# tm8_racingStripes.net
KiCad netlist of a schematic drawn in EAGLE
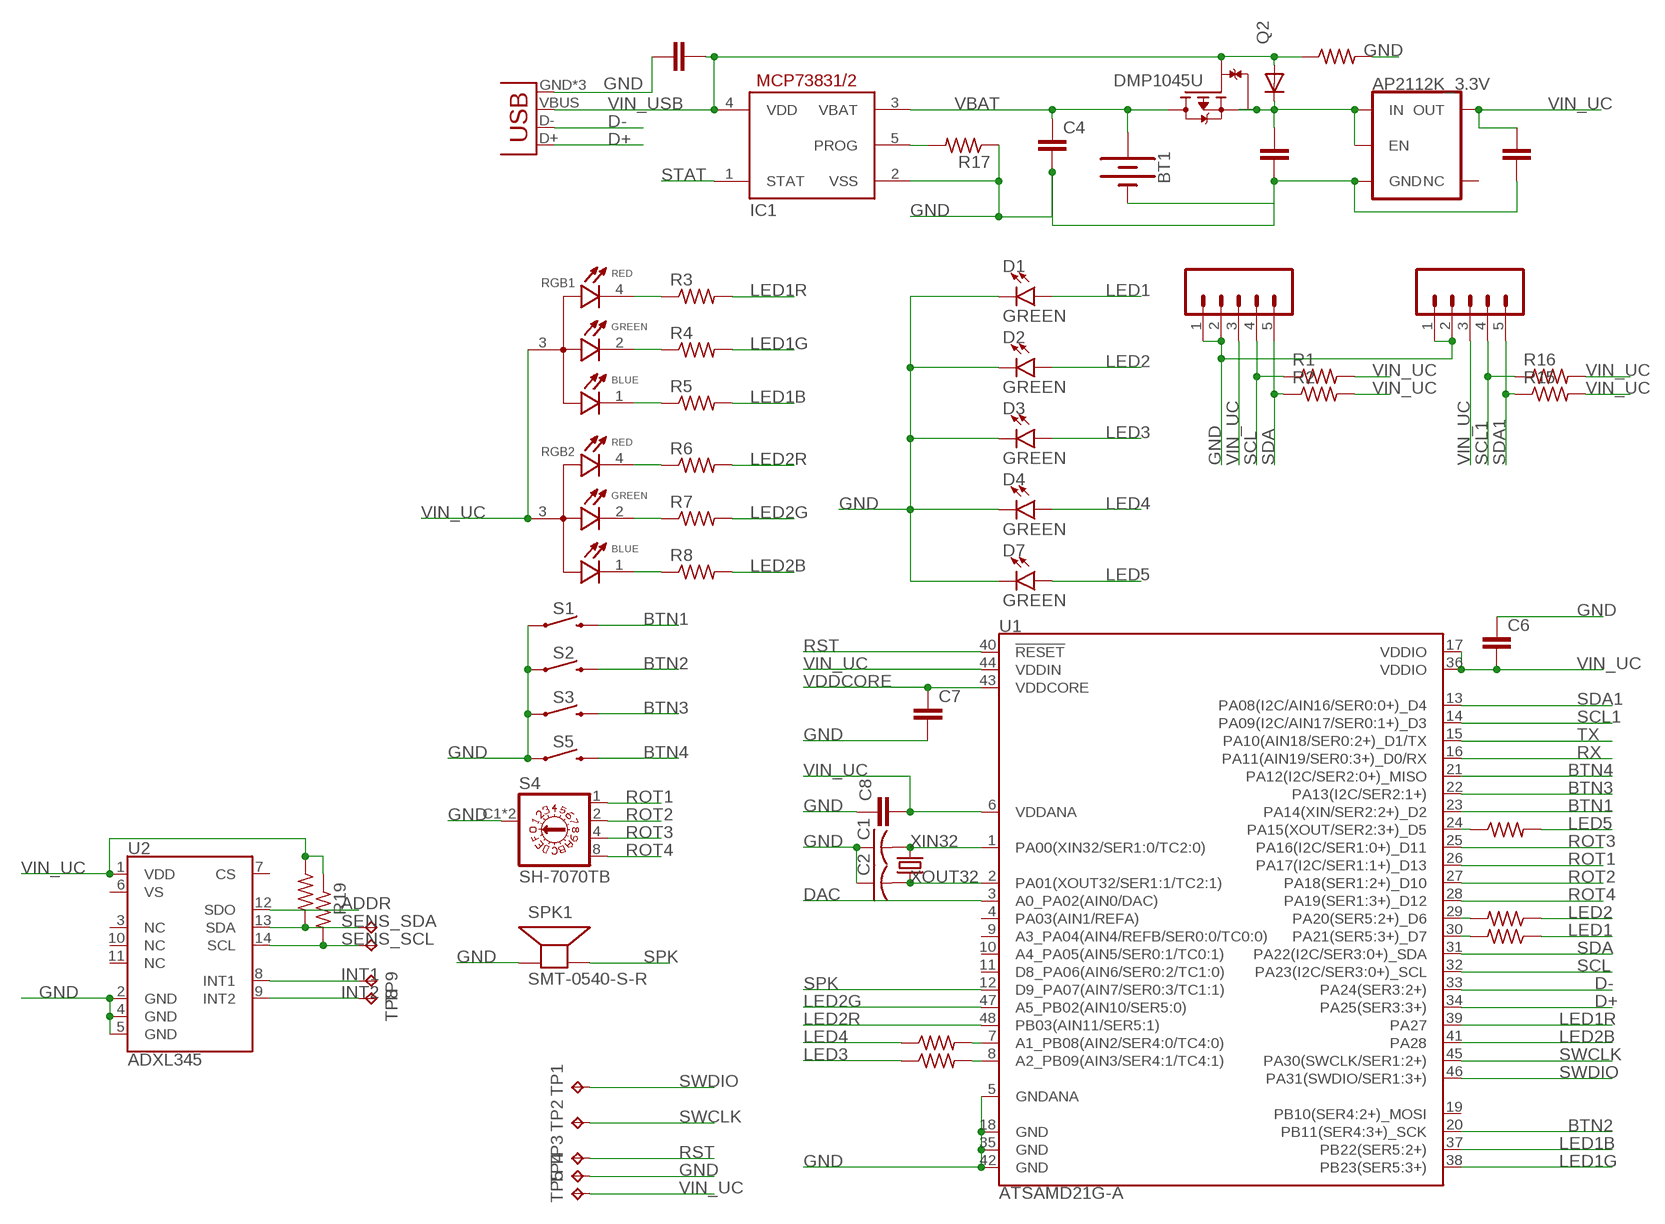
[diagram p0: schematic, sheet 1]

(export (version "E")
  (design (tool "Eeschema 10.0.6"))
  (components
    (comp (ref "AP2112K_3.3V")
      (value "3.3V")
      (footprint "eagle-import:SOT23-5")
      (libsource (lib "eagle-import") (part "V_REG_AP2112K-3.3V"))
    )
    (comp (ref "BT1")
      (value "BATTERY-20MM_SMD_4LEGS_OVERPASTE_INNER")
      (footprint "eagle-import:BATTCON_20MM_4LEGS_OVERPASTE_INNER")
      (libsource (lib "eagle-import") (part "BATTERY-20MM_SMD_4LEGS_OVERPASTE_INNER"))
    )
    (comp (ref "C1")
      (value "C-USC0603")
      (footprint "eagle-import:C0603")
      (libsource (lib "eagle-import") (part "C-USC0603"))
    )
    (comp (ref "C2")
      (value "C-USC0603")
      (footprint "eagle-import:C0603")
      (libsource (lib "eagle-import") (part "C-USC0603"))
    )
    (comp (ref "C3")
      (value "C-EUC0603")
      (footprint "eagle-import:C0603")
      (libsource (lib "eagle-import") (part "C-EUC0603"))
    )
    (comp (ref "C4")
      (value "C-EUC0603")
      (footprint "eagle-import:C0603")
      (libsource (lib "eagle-import") (part "C-EUC0603"))
    )
    (comp (ref "C5")
      (value "C-EUC0603")
      (footprint "eagle-import:C0603")
      (libsource (lib "eagle-import") (part "C-EUC0603"))
    )
    (comp (ref "C6")
      (value "C-EUC0603")
      (footprint "eagle-import:C0603")
      (libsource (lib "eagle-import") (part "C-EUC0603"))
    )
    (comp (ref "C7")
      (value "C-EUC0603")
      (footprint "eagle-import:C0603")
      (libsource (lib "eagle-import") (part "C-EUC0603"))
    )
    (comp (ref "C8")
      (value "C-EUC0603")
      (footprint "eagle-import:C0603")
      (libsource (lib "eagle-import") (part "C-EUC0603"))
    )
    (comp (ref "C9")
      (value "C-EUC0603")
      (footprint "eagle-import:C0603")
      (libsource (lib "eagle-import") (part "C-EUC0603"))
    )
    (comp (ref "D1")
      (value "GREEN")
      (footprint "eagle-import:LED-1206")
      (libsource (lib "eagle-import") (part "LED-GREEN1206"))
    )
    (comp (ref "D2")
      (value "GREEN")
      (footprint "eagle-import:LED-1206")
      (libsource (lib "eagle-import") (part "LED-GREEN1206"))
    )
    (comp (ref "D3")
      (value "GREEN")
      (footprint "eagle-import:LED-1206")
      (libsource (lib "eagle-import") (part "LED-GREEN1206"))
    )
    (comp (ref "D4")
      (value "GREEN")
      (footprint "eagle-import:LED-1206")
      (libsource (lib "eagle-import") (part "LED-GREEN1206"))
    )
    (comp (ref "D7")
      (value "GREEN")
      (footprint "eagle-import:LED-1206")
      (libsource (lib "eagle-import") (part "LED-GREEN1206"))
    )
    (comp (ref "D8")
      (value "DIODESOD-323F")
      (footprint "eagle-import:SOD-323F")
      (libsource (lib "eagle-import") (part "DIODESOD-323F"))
    )
    (comp (ref "IC1")
      (value "MCP73831/OT")
      (footprint "eagle-import:SOT23-5L")
      (libsource (lib "eagle-import") (part "MCP73831/OT"))
    )
    (comp (ref "JP2")
      (value "USB-MICROB")
      (footprint "eagle-import:USB-MICROB")
      (libsource (lib "eagle-import") (part "USB-MICROB"))
    )
    (comp (ref "LCD1")
      (value "CONN_05VERT_FEMALE_HEADER")
      (footprint "eagle-import:1X05_SMD_VERTICAL_COMBO")
      (libsource (lib "eagle-import") (part "CONN_05VERT_FEMALE_HEADER"))
    )
    (comp (ref "LCD2")
      (value "CONN_05VERT_FEMALE_HEADER")
      (footprint "eagle-import:1X05_SMD_VERTICAL_COMBO")
      (libsource (lib "eagle-import") (part "CONN_05VERT_FEMALE_HEADER"))
    )
    (comp (ref "Q2")
      (value "DMP1045U")
      (footprint "eagle-import:SOT91P240X110-3N")
      (fields (field (name "MF") "Diodes Inc."))
      (libsource (lib "eagle-import") (part "DMP1045U"))
    )
    (comp (ref "R1")
      (value "R-US_R0603")
      (footprint "eagle-import:R0603")
      (libsource (lib "eagle-import") (part "rcl_334_R-US_R0603"))
    )
    (comp (ref "R2")
      (value "R-US_R0603")
      (footprint "eagle-import:R0603")
      (libsource (lib "eagle-import") (part "rcl_334_R-US_R0603"))
    )
    (comp (ref "R3")
      (value "R-US_R0603")
      (footprint "eagle-import:R0603")
      (libsource (lib "eagle-import") (part "rcl_334_R-US_R0603"))
    )
    (comp (ref "R4")
      (value "R-US_R0603")
      (footprint "eagle-import:R0603")
      (libsource (lib "eagle-import") (part "rcl_334_R-US_R0603"))
    )
    (comp (ref "R5")
      (value "R-US_R0603")
      (footprint "eagle-import:R0603")
      (libsource (lib "eagle-import") (part "rcl_334_R-US_R0603"))
    )
    (comp (ref "R6")
      (value "R-US_R0603")
      (footprint "eagle-import:R0603")
      (libsource (lib "eagle-import") (part "rcl_334_R-US_R0603"))
    )
    (comp (ref "R7")
      (value "R-US_R0603")
      (footprint "eagle-import:R0603")
      (libsource (lib "eagle-import") (part "rcl_334_R-US_R0603"))
    )
    (comp (ref "R8")
      (value "R-US_R0603")
      (footprint "eagle-import:R0603")
      (libsource (lib "eagle-import") (part "rcl_334_R-US_R0603"))
    )
    (comp (ref "R9")
      (value "R-US_R0603")
      (footprint "eagle-import:R0603")
      (libsource (lib "eagle-import") (part "rcl_334_R-US_R0603"))
    )
    (comp (ref "R10")
      (value "R-US_R0603")
      (footprint "eagle-import:R0603")
      (libsource (lib "eagle-import") (part "rcl_334_R-US_R0603"))
    )
    (comp (ref "R11")
      (value "R-US_R0603")
      (footprint "eagle-import:R0603")
      (libsource (lib "eagle-import") (part "rcl_334_R-US_R0603"))
    )
    (comp (ref "R12")
      (value "R-US_R0603")
      (footprint "eagle-import:R0603")
      (libsource (lib "eagle-import") (part "rcl_334_R-US_R0603"))
    )
    (comp (ref "R13")
      (value "R-US_R0603")
      (footprint "eagle-import:R0603")
      (libsource (lib "eagle-import") (part "rcl_334_R-US_R0603"))
    )
    (comp (ref "R14")
      (value "R-US_R0603")
      (footprint "eagle-import:R0603")
      (libsource (lib "eagle-import") (part "R-US_R0603"))
    )
    (comp (ref "R15")
      (value "R-US_R0603")
      (footprint "eagle-import:R0603")
      (libsource (lib "eagle-import") (part "rcl_334_R-US_R0603"))
    )
    (comp (ref "R16")
      (value "R-US_R0603")
      (footprint "eagle-import:R0603")
      (libsource (lib "eagle-import") (part "rcl_334_R-US_R0603"))
    )
    (comp (ref "R17")
      (value "R-US_R0603")
      (footprint "eagle-import:R0603")
      (libsource (lib "eagle-import") (part "adafruit_25768682_R-US_R0603"))
    )
    (comp (ref "R18")
      (value "R-US_R0603")
      (footprint "eagle-import:R0603")
      (libsource (lib "eagle-import") (part "rcl_334_R-US_R0603"))
    )
    (comp (ref "R19")
      (value "R-US_R0603")
      (footprint "eagle-import:R0603")
      (libsource (lib "eagle-import") (part "rcl_334_R-US_R0603"))
    )
    (comp (ref "RGB1")
      (value "EAST1616RGBA3")
      (footprint "eagle-import:LED_EAST1616RGBA3")
      (fields (field (name "MF") "Everlight Electronics"))
      (libsource (lib "eagle-import") (part "EAST1616RGBA3"))
    )
    (comp (ref "RGB2")
      (value "EAST1616RGBA3")
      (footprint "eagle-import:LED_EAST1616RGBA3")
      (fields (field (name "MF") "Everlight Electronics"))
      (libsource (lib "eagle-import") (part "EAST1616RGBA3"))
    )
    (comp (ref "S1")
      (value "MOMENTARY-SWITCH-SPST-SMD-6.0X3.5MM")
      (footprint "eagle-import:TACTILE_SWITCH_SMD_6.0X3.5MM")
      (libsource (lib "eagle-import") (part "MOMENTARY-SWITCH-SPST-SMD-6.0X3.5MM"))
    )
    (comp (ref "S2")
      (value "MOMENTARY-SWITCH-SPST-SMD-6.0X3.5MM")
      (footprint "eagle-import:TACTILE_SWITCH_SMD_6.0X3.5MM")
      (libsource (lib "eagle-import") (part "MOMENTARY-SWITCH-SPST-SMD-6.0X3.5MM"))
    )
    (comp (ref "S3")
      (value "MOMENTARY-SWITCH-SPST-SMD-6.0X3.5MM")
      (footprint "eagle-import:TACTILE_SWITCH_SMD_6.0X3.5MM")
      (libsource (lib "eagle-import") (part "MOMENTARY-SWITCH-SPST-SMD-6.0X3.5MM"))
    )
    (comp (ref "S4")
      (value "SH-7070TB")
      (footprint "eagle-import:SH-7070B")
      (fields (field (name "MF") "Nidec Copal"))
      (libsource (lib "eagle-import") (part "SH-7070TB"))
    )
    (comp (ref "S5")
      (value "MOMENTARY-SWITCH-SPST-SMD-6.0X3.5MM")
      (footprint "eagle-import:TACTILE_SWITCH_SMD_6.0X3.5MM")
      (libsource (lib "eagle-import") (part "MOMENTARY-SWITCH-SPST-SMD-6.0X3.5MM"))
    )
    (comp (ref "SPK1")
      (value "SMT-0540-S-R")
      (footprint "eagle-import:SMT-0540-S-R")
      (fields (field (name "MF") "PUI"))
      (libsource (lib "eagle-import") (part "SMT-0540-S-R"))
    )
    (comp (ref "TP1")
      (value "TPTP10R")
      (footprint "eagle-import:TP10R")
      (libsource (lib "eagle-import") (part "TPTP10R"))
    )
    (comp (ref "TP2")
      (value "TPTP10R")
      (footprint "eagle-import:TP10R")
      (libsource (lib "eagle-import") (part "TPTP10R"))
    )
    (comp (ref "TP3")
      (value "TPTP10R")
      (footprint "eagle-import:TP10R")
      (libsource (lib "eagle-import") (part "TPTP10R"))
    )
    (comp (ref "TP4")
      (value "TPTP10R")
      (footprint "eagle-import:TP10R")
      (libsource (lib "eagle-import") (part "TPTP10R"))
    )
    (comp (ref "TP5")
      (value "TPTP10R")
      (footprint "eagle-import:TP10R")
      (libsource (lib "eagle-import") (part "TPTP10R"))
    )
    (comp (ref "TP6")
      (value "TPTP10R")
      (footprint "eagle-import:TP10R")
      (libsource (lib "eagle-import") (part "TPTP10R"))
    )
    (comp (ref "TP7")
      (value "TPTP10R")
      (footprint "eagle-import:TP10R")
      (libsource (lib "eagle-import") (part "TPTP10R"))
    )
    (comp (ref "TP8")
      (value "TPTP10R")
      (footprint "eagle-import:TP10R")
      (libsource (lib "eagle-import") (part "TPTP10R"))
    )
    (comp (ref "TP9")
      (value "TPTP10R")
      (footprint "eagle-import:TP10R")
      (libsource (lib "eagle-import") (part "TPTP10R"))
    )
    (comp (ref "U1")
      (value "ATSAMD21G-A")
      (footprint "eagle-import:TQFP-48")
      (libsource (lib "eagle-import") (part "ATSAMD21G-A"))
    )
    (comp (ref "U2")
      (value "ADXL345")
      (footprint "eagle-import:LGA-14")
      (libsource (lib "eagle-import") (part "ADXL345"))
    )
    (comp (ref "Y1")
      (value "32.768kHz")
      (footprint "eagle-import:CRYSTAL-SMD-3.2X1.5MM")
      (libsource (lib "eagle-import") (part "CRYSTAL-32.768KHZSMD-3.2X1.5"))
    )
  )
  (nets
    (net (code "1") (name "/ADDR") (class "Default")
      (node (ref "U2") (pin "12") (pinfunction "SDO_12") (pintype "bidirectional"))
    )
    (net (code "2") (name "/BTN1") (class "Default")
      (node (ref "S1") (pin "2") (pinfunction "2_2") (pintype "passive"))
      (node (ref "U1") (pin "23") (pinfunction "PA14(XIN/SER2:2+)_D2_23") (pintype "bidirectional"))
    )
    (net (code "3") (name "/BTN2") (class "Default")
      (node (ref "S2") (pin "2") (pinfunction "2_2") (pintype "passive"))
      (node (ref "U1") (pin "20") (pinfunction "PB11(SER4:3+)_SCK_20") (pintype "bidirectional"))
    )
    (net (code "4") (name "/BTN3") (class "Default")
      (node (ref "S3") (pin "2") (pinfunction "2_2") (pintype "passive"))
      (node (ref "U1") (pin "22") (pinfunction "PA13(I2C/SER2:1+)_22") (pintype "bidirectional"))
    )
    (net (code "5") (name "/BTN4") (class "Default")
      (node (ref "S5") (pin "2") (pinfunction "2_2") (pintype "passive"))
      (node (ref "U1") (pin "21") (pinfunction "PA12(I2C/SER2:0+)_MISO_21") (pintype "bidirectional"))
    )
    (net (code "6") (name "/D+") (class "Default")
      (node (ref "JP2") (pin "D+") (pinfunction "D+_D+") (pintype "bidirectional"))
      (node (ref "U1") (pin "34") (pinfunction "PA25(SER3:3+)_34") (pintype "bidirectional"))
    )
    (net (code "7") (name "/D-") (class "Default")
      (node (ref "JP2") (pin "D-") (pinfunction "D-_D-") (pintype "bidirectional"))
      (node (ref "U1") (pin "33") (pinfunction "PA24(SER3:2+)_33") (pintype "bidirectional"))
    )
    (net (code "8") (name "/DAC") (class "Default")
      (node (ref "U1") (pin "3") (pinfunction "A0_PA02(AIN0/DAC)_3") (pintype "bidirectional"))
    )
    (net (code "9") (name "/GND") (class "Default")
      (node (ref "AP2112K_3.3V") (pin "2") (pinfunction "GND_2") (pintype "input"))
      (node (ref "BT1") (pin "2") (pinfunction "-_2") (pintype "power_in"))
      (node (ref "C1") (pin "1") (pinfunction "1_1") (pintype "passive"))
      (node (ref "C2") (pin "1") (pinfunction "1_1") (pintype "passive"))
      (node (ref "C3") (pin "1") (pinfunction "1_1") (pintype "passive"))
      (node (ref "C4") (pin "2") (pinfunction "2_2") (pintype "passive"))
      (node (ref "C5") (pin "2") (pinfunction "2_2") (pintype "passive"))
      (node (ref "C6") (pin "1") (pinfunction "1_1") (pintype "passive"))
      (node (ref "C7") (pin "2") (pinfunction "2_2") (pintype "passive"))
      (node (ref "C8") (pin "1") (pinfunction "1_1") (pintype "passive"))
      (node (ref "C9") (pin "2") (pinfunction "2_2") (pintype "passive"))
      (node (ref "D1") (pin "C") (pinfunction "C_C") (pintype "passive"))
      (node (ref "D2") (pin "C") (pinfunction "C_C") (pintype "passive"))
      (node (ref "D3") (pin "C") (pinfunction "C_C") (pintype "passive"))
      (node (ref "D4") (pin "C") (pinfunction "C_C") (pintype "passive"))
      (node (ref "D7") (pin "C") (pinfunction "C_C") (pintype "passive"))
      (node (ref "IC1") (pin "2") (pinfunction "VSS_2") (pintype "power_in"))
      (node (ref "JP2") (pin "GND") (pinfunction "GND_GND") (pintype "bidirectional"))
      (node (ref "JP2") (pin "MT1") (pinfunction "GND_MT1") (pintype "bidirectional"))
      (node (ref "JP2") (pin "MT2") (pinfunction "GND_MT2") (pintype "bidirectional"))
      (node (ref "LCD1") (pin "1") (pinfunction "1_1") (pintype "passive"))
      (node (ref "LCD1") (pin "2") (pinfunction "2_2") (pintype "passive"))
      (node (ref "LCD2") (pin "1") (pinfunction "1_1") (pintype "passive"))
      (node (ref "LCD2") (pin "2") (pinfunction "2_2") (pintype "passive"))
      (node (ref "R14") (pin "2") (pinfunction "2_2") (pintype "passive"))
      (node (ref "R17") (pin "1") (pinfunction "1_1") (pintype "passive"))
      (node (ref "S1") (pin "1") (pinfunction "1_1") (pintype "passive"))
      (node (ref "S2") (pin "1") (pinfunction "1_1") (pintype "passive"))
      (node (ref "S3") (pin "1") (pinfunction "1_1") (pintype "passive"))
      (node (ref "S4") (pin "C1") (pinfunction "C_C1") (pintype "passive"))
      (node (ref "S4") (pin "C2") (pinfunction "C_C2") (pintype "passive"))
      (node (ref "S5") (pin "1") (pinfunction "1_1") (pintype "passive"))
      (node (ref "SPK1") (pin "-") (pinfunction "+_-") (pintype "passive"))
      (node (ref "TP4") (pin "TP") (pinfunction "TP_TP") (pintype "input"))
      (node (ref "U1") (pin "18") (pinfunction "GND_18") (pintype "bidirectional"))
      (node (ref "U1") (pin "35") (pinfunction "GND_35") (pintype "bidirectional"))
      (node (ref "U1") (pin "42") (pinfunction "GND_42") (pintype "bidirectional"))
      (node (ref "U1") (pin "5") (pinfunction "GNDANA_5") (pintype "bidirectional"))
      (node (ref "U2") (pin "2") (pinfunction "GND_2") (pintype "bidirectional"))
      (node (ref "U2") (pin "4") (pinfunction "GND_4") (pintype "bidirectional"))
      (node (ref "U2") (pin "5") (pinfunction "GND_5") (pintype "bidirectional"))
    )
    (net (code "10") (name "/INT1") (class "Default")
      (node (ref "TP9") (pin "TP") (pinfunction "TP_TP") (pintype "input"))
      (node (ref "U2") (pin "8") (pinfunction "INT1_8") (pintype "bidirectional"))
    )
    (net (code "11") (name "/INT2") (class "Default")
      (node (ref "TP8") (pin "TP") (pinfunction "TP_TP") (pintype "input"))
      (node (ref "U2") (pin "9") (pinfunction "INT2_9") (pintype "bidirectional"))
    )
    (net (code "12") (name "/LED1") (class "Default")
      (node (ref "D1") (pin "A") (pinfunction "A_A") (pintype "passive"))
      (node (ref "R9") (pin "1") (pinfunction "1_1") (pintype "passive"))
    )
    (net (code "13") (name "/LED1B") (class "Default")
      (node (ref "R5") (pin "2") (pinfunction "2_2") (pintype "passive"))
      (node (ref "U1") (pin "37") (pinfunction "PB22(SER5:2+)_37") (pintype "bidirectional"))
    )
    (net (code "14") (name "/LED1G") (class "Default")
      (node (ref "R4") (pin "2") (pinfunction "2_2") (pintype "passive"))
      (node (ref "U1") (pin "38") (pinfunction "PB23(SER5:3+)_38") (pintype "bidirectional"))
    )
    (net (code "15") (name "/LED1R") (class "Default")
      (node (ref "R3") (pin "2") (pinfunction "2_2") (pintype "passive"))
      (node (ref "U1") (pin "39") (pinfunction "PA27_39") (pintype "bidirectional"))
    )
    (net (code "16") (name "/LED2") (class "Default")
      (node (ref "D2") (pin "A") (pinfunction "A_A") (pintype "passive"))
      (node (ref "R10") (pin "1") (pinfunction "1_1") (pintype "passive"))
    )
    (net (code "17") (name "/LED2B") (class "Default")
      (node (ref "R8") (pin "2") (pinfunction "2_2") (pintype "passive"))
      (node (ref "U1") (pin "41") (pinfunction "PA28_41") (pintype "bidirectional"))
    )
    (net (code "18") (name "/LED2G") (class "Default")
      (node (ref "R7") (pin "2") (pinfunction "2_2") (pintype "passive"))
      (node (ref "U1") (pin "47") (pinfunction "A5_PB02(AIN10/SER5:0)_47") (pintype "bidirectional"))
    )
    (net (code "19") (name "/LED2R") (class "Default")
      (node (ref "R6") (pin "2") (pinfunction "2_2") (pintype "passive"))
      (node (ref "U1") (pin "48") (pinfunction "PB03(AIN11/SER5:1)_48") (pintype "bidirectional"))
    )
    (net (code "20") (name "/LED3") (class "Default")
      (node (ref "D3") (pin "A") (pinfunction "A_A") (pintype "passive"))
      (node (ref "R11") (pin "1") (pinfunction "1_1") (pintype "passive"))
    )
    (net (code "21") (name "/LED4") (class "Default")
      (node (ref "D4") (pin "A") (pinfunction "A_A") (pintype "passive"))
      (node (ref "R12") (pin "1") (pinfunction "1_1") (pintype "passive"))
    )
    (net (code "22") (name "/LED5") (class "Default")
      (node (ref "D7") (pin "A") (pinfunction "A_A") (pintype "passive"))
      (node (ref "R13") (pin "2") (pinfunction "2_2") (pintype "passive"))
    )
    (net (code "23") (name "/ROT1") (class "Default")
      (node (ref "S4") (pin "1") (pinfunction "1_1") (pintype "passive"))
      (node (ref "U1") (pin "26") (pinfunction "PA17(I2C/SER1:1+)_D13_26") (pintype "bidirectional"))
    )
    (net (code "24") (name "/ROT2") (class "Default")
      (node (ref "S4") (pin "2") (pinfunction "2_2") (pintype "passive"))
      (node (ref "U1") (pin "27") (pinfunction "PA18(SER1:2+)_D10_27") (pintype "bidirectional"))
    )
    (net (code "25") (name "/ROT3") (class "Default")
      (node (ref "S4") (pin "4") (pinfunction "4_4") (pintype "passive"))
      (node (ref "U1") (pin "25") (pinfunction "PA16(I2C/SER1:0+)_D11_25") (pintype "bidirectional"))
    )
    (net (code "26") (name "/ROT4") (class "Default")
      (node (ref "S4") (pin "8") (pinfunction "8_8") (pintype "passive"))
      (node (ref "U1") (pin "28") (pinfunction "PA19(SER1:3+)_D12_28") (pintype "bidirectional"))
    )
    (net (code "27") (name "/RST") (class "Default")
      (node (ref "TP3") (pin "TP") (pinfunction "TP_TP") (pintype "input"))
      (node (ref "U1") (pin "40") (pinfunction "~{RESET}_40") (pintype "bidirectional"))
    )
    (net (code "28") (name "/RX") (class "Default")
      (node (ref "U1") (pin "16") (pinfunction "PA11(AIN19/SER0:3+)_D0/RX_16") (pintype "bidirectional"))
    )
    (net (code "29") (name "/SCL") (class "Default")
      (node (ref "LCD1") (pin "4") (pinfunction "4_4") (pintype "passive"))
      (node (ref "R1") (pin "1") (pinfunction "1_1") (pintype "passive"))
      (node (ref "U1") (pin "32") (pinfunction "PA23(I2C/SER3:0+)_SCL_32") (pintype "bidirectional"))
    )
    (net (code "30") (name "/SCL1") (class "Default")
      (node (ref "LCD2") (pin "4") (pinfunction "4_4") (pintype "passive"))
      (node (ref "R16") (pin "1") (pinfunction "1_1") (pintype "passive"))
      (node (ref "U1") (pin "14") (pinfunction "PA09(I2C/AIN17/SER0:1+)_D3_14") (pintype "bidirectional"))
    )
    (net (code "31") (name "/SDA") (class "Default")
      (node (ref "LCD1") (pin "5") (pinfunction "5_5") (pintype "passive"))
      (node (ref "R2") (pin "1") (pinfunction "1_1") (pintype "passive"))
      (node (ref "U1") (pin "31") (pinfunction "PA22(I2C/SER3:0+)_SDA_31") (pintype "bidirectional"))
    )
    (net (code "32") (name "/SDA1") (class "Default")
      (node (ref "LCD2") (pin "5") (pinfunction "5_5") (pintype "passive"))
      (node (ref "R15") (pin "1") (pinfunction "1_1") (pintype "passive"))
      (node (ref "U1") (pin "13") (pinfunction "PA08(I2C/AIN16/SER0:0+)_D4_13") (pintype "bidirectional"))
    )
    (net (code "33") (name "/SENS_SCL") (class "Default")
      (node (ref "R19") (pin "2") (pinfunction "2_2") (pintype "passive"))
      (node (ref "TP6") (pin "TP") (pinfunction "TP_TP") (pintype "input"))
      (node (ref "U2") (pin "14") (pinfunction "SCL_14") (pintype "bidirectional"))
    )
    (net (code "34") (name "/SENS_SDA") (class "Default")
      (node (ref "R18") (pin "2") (pinfunction "2_2") (pintype "passive"))
      (node (ref "TP7") (pin "TP") (pinfunction "TP_TP") (pintype "input"))
      (node (ref "U2") (pin "13") (pinfunction "SDA_13") (pintype "bidirectional"))
    )
    (net (code "35") (name "/SPK") (class "Default")
      (node (ref "SPK1") (pin "+") (pinfunction "-_+") (pintype "passive"))
      (node (ref "U1") (pin "12") (pinfunction "D9_PA07(AIN7/SER0:3/TC1:1)_12") (pintype "bidirectional"))
    )
    (net (code "36") (name "/STAT") (class "Default")
      (node (ref "IC1") (pin "1") (pinfunction "STAT_1") (pintype "output"))
    )
    (net (code "37") (name "/SWCLK") (class "Default")
      (node (ref "TP2") (pin "TP") (pinfunction "TP_TP") (pintype "input"))
      (node (ref "U1") (pin "45") (pinfunction "PA30(SWCLK/SER1:2+)_45") (pintype "bidirectional"))
    )
    (net (code "38") (name "/SWDIO") (class "Default")
      (node (ref "TP1") (pin "TP") (pinfunction "TP_TP") (pintype "input"))
      (node (ref "U1") (pin "46") (pinfunction "PA31(SWDIO/SER1:3+)_46") (pintype "bidirectional"))
    )
    (net (code "39") (name "/TX") (class "Default")
      (node (ref "U1") (pin "15") (pinfunction "PA10(AIN18/SER0:2+)_D1/TX_15") (pintype "bidirectional"))
    )
    (net (code "40") (name "/VBAT") (class "Default")
      (node (ref "BT1") (pin "1") (pinfunction "+_1") (pintype "power_in"))
      (node (ref "C4") (pin "1") (pinfunction "1_1") (pintype "passive"))
      (node (ref "IC1") (pin "3") (pinfunction "VBAT_3") (pintype "bidirectional"))
      (node (ref "Q2") (pin "3") (pinfunction "D_3") (pintype "passive"))
    )
    (net (code "41") (name "/VDDCORE") (class "Default")
      (node (ref "C7") (pin "1") (pinfunction "1_1") (pintype "passive"))
      (node (ref "U1") (pin "43") (pinfunction "VDDCORE_43") (pintype "bidirectional"))
    )
    (net (code "42") (name "/VIN_UC") (class "Default")
      (node (ref "AP2112K_3.3V") (pin "5") (pinfunction "OUT_5") (pintype "passive"))
      (node (ref "C5") (pin "1") (pinfunction "1_1") (pintype "passive"))
      (node (ref "C6") (pin "2") (pinfunction "2_2") (pintype "passive"))
      (node (ref "C8") (pin "2") (pinfunction "2_2") (pintype "passive"))
      (node (ref "LCD1") (pin "3") (pinfunction "3_3") (pintype "passive"))
      (node (ref "LCD2") (pin "3") (pinfunction "3_3") (pintype "passive"))
      (node (ref "R1") (pin "2") (pinfunction "2_2") (pintype "passive"))
      (node (ref "R15") (pin "2") (pinfunction "2_2") (pintype "passive"))
      (node (ref "R16") (pin "2") (pinfunction "2_2") (pintype "passive"))
      (node (ref "R18") (pin "1") (pinfunction "1_1") (pintype "passive"))
      (node (ref "R19") (pin "1") (pinfunction "1_1") (pintype "passive"))
      (node (ref "R2") (pin "2") (pinfunction "2_2") (pintype "passive"))
      (node (ref "RGB1") (pin "3") (pinfunction "A_3") (pintype "passive"))
      (node (ref "RGB2") (pin "3") (pinfunction "A_3") (pintype "passive"))
      (node (ref "TP5") (pin "TP") (pinfunction "TP_TP") (pintype "input"))
      (node (ref "U1") (pin "17") (pinfunction "VDDIO_17") (pintype "bidirectional"))
      (node (ref "U1") (pin "36") (pinfunction "VDDIO_36") (pintype "bidirectional"))
      (node (ref "U1") (pin "44") (pinfunction "VDDIN_44") (pintype "bidirectional"))
      (node (ref "U1") (pin "6") (pinfunction "VDDANA_6") (pintype "bidirectional"))
      (node (ref "U2") (pin "1") (pinfunction "VDD_1") (pintype "bidirectional"))
    )
    (net (code "43") (name "/VIN_USB") (class "Default")
      (node (ref "C3") (pin "2") (pinfunction "2_2") (pintype "passive"))
      (node (ref "D8") (pin "A") (pinfunction "A_A") (pintype "passive"))
      (node (ref "IC1") (pin "4") (pinfunction "VDD_4") (pintype "power_in"))
      (node (ref "JP2") (pin "VBUS") (pinfunction "VBUS_VBUS") (pintype "bidirectional"))
      (node (ref "Q2") (pin "1") (pinfunction "G_1") (pintype "passive"))
      (node (ref "R14") (pin "1") (pinfunction "1_1") (pintype "passive"))
    )
    (net (code "44") (name "/XIN32") (class "Default")
      (node (ref "C1") (pin "2") (pinfunction "2_2") (pintype "passive"))
      (node (ref "U1") (pin "1") (pinfunction "PA00(XIN32/SER1:0/TC2:0)_1") (pintype "bidirectional"))
      (node (ref "Y1") (pin "P$2") (pinfunction "2_P$2") (pintype "passive"))
    )
    (net (code "45") (name "/XOUT32") (class "Default")
      (node (ref "C2") (pin "2") (pinfunction "2_2") (pintype "passive"))
      (node (ref "U1") (pin "2") (pinfunction "PA01(XOUT32/SER1:1/TC2:1)_2") (pintype "bidirectional"))
      (node (ref "Y1") (pin "P$1") (pinfunction "1_P$1") (pintype "passive"))
    )
    (net (code "46") (name "Net-(AP2112K_3.3V-EN)") (class "Default")
      (node (ref "AP2112K_3.3V") (pin "1") (pinfunction "IN_1") (pintype "input"))
      (node (ref "AP2112K_3.3V") (pin "3") (pinfunction "EN_3") (pintype "input"))
      (node (ref "C9") (pin "1") (pinfunction "1_1") (pintype "passive"))
      (node (ref "D8") (pin "C") (pinfunction "C_C") (pintype "passive"))
      (node (ref "Q2") (pin "2") (pinfunction "S_2") (pintype "passive"))
    )
    (net (code "47") (name "Net-(IC1-PROG)") (class "Default")
      (node (ref "IC1") (pin "5") (pinfunction "PROG_5") (pintype "input"))
      (node (ref "R17") (pin "2") (pinfunction "2_2") (pintype "passive"))
    )
    (net (code "48") (name "Net-(RGB1-B_C)") (class "Default")
      (node (ref "R5") (pin "1") (pinfunction "1_1") (pintype "passive"))
      (node (ref "RGB1") (pin "1") (pinfunction "B_C_1") (pintype "passive"))
    )
    (net (code "49") (name "Net-(RGB1-G_C)") (class "Default")
      (node (ref "R4") (pin "1") (pinfunction "1_1") (pintype "passive"))
      (node (ref "RGB1") (pin "2") (pinfunction "G_C_2") (pintype "passive"))
    )
    (net (code "50") (name "Net-(RGB1-R_C)") (class "Default")
      (node (ref "R3") (pin "1") (pinfunction "1_1") (pintype "passive"))
      (node (ref "RGB1") (pin "4") (pinfunction "R_C_4") (pintype "passive"))
    )
    (net (code "51") (name "Net-(RGB2-B_C)") (class "Default")
      (node (ref "R8") (pin "1") (pinfunction "1_1") (pintype "passive"))
      (node (ref "RGB2") (pin "1") (pinfunction "B_C_1") (pintype "passive"))
    )
    (net (code "52") (name "Net-(RGB2-G_C)") (class "Default")
      (node (ref "R7") (pin "1") (pinfunction "1_1") (pintype "passive"))
      (node (ref "RGB2") (pin "2") (pinfunction "G_C_2") (pintype "passive"))
    )
    (net (code "53") (name "Net-(RGB2-R_C)") (class "Default")
      (node (ref "R6") (pin "1") (pinfunction "1_1") (pintype "passive"))
      (node (ref "RGB2") (pin "4") (pinfunction "R_C_4") (pintype "passive"))
    )
    (net (code "54") (name "Net-(U1-A1_PB08(AIN2{slash}SER4:0{slash}TC4:0))") (class "Default")
      (node (ref "R12") (pin "2") (pinfunction "2_2") (pintype "passive"))
      (node (ref "U1") (pin "7") (pinfunction "A1_PB08(AIN2/SER4:0/TC4:0)_7") (pintype "bidirectional"))
    )
    (net (code "55") (name "Net-(U1-A2_PB09(AIN3{slash}SER4:1{slash}TC4:1))") (class "Default")
      (node (ref "R11") (pin "2") (pinfunction "2_2") (pintype "passive"))
      (node (ref "U1") (pin "8") (pinfunction "A2_PB09(AIN3/SER4:1/TC4:1)_8") (pintype "bidirectional"))
    )
    (net (code "56") (name "Net-(U1-PA15(XOUT{slash}SER2:3+)_D5)") (class "Default")
      (node (ref "R13") (pin "1") (pinfunction "1_1") (pintype "passive"))
      (node (ref "U1") (pin "24") (pinfunction "PA15(XOUT/SER2:3+)_D5_24") (pintype "bidirectional"))
    )
    (net (code "57") (name "Net-(U1-PA20(SER5:2+)_D6)") (class "Default")
      (node (ref "R10") (pin "2") (pinfunction "2_2") (pintype "passive"))
      (node (ref "U1") (pin "29") (pinfunction "PA20(SER5:2+)_D6_29") (pintype "bidirectional"))
    )
    (net (code "58") (name "Net-(U1-PA21(SER5:3+)_D7)") (class "Default")
      (node (ref "R9") (pin "2") (pinfunction "2_2") (pintype "passive"))
      (node (ref "U1") (pin "30") (pinfunction "PA21(SER5:3+)_D7_30") (pintype "bidirectional"))
    )
    (net (code "59") (name "unconnected-(AP2112K_3.3V-NC-Pad4)") (class "Default")
      (node (ref "AP2112K_3.3V") (pin "4") (pinfunction "NC_4") (pintype "no_connect"))
    )
    (net (code "60") (name "unconnected-(U1-A3_PA04(AIN4{slash}REFB{slash}SER0:0{slash}TC0:0)-Pad9)") (class "Default")
      (node (ref "U1") (pin "9") (pinfunction "A3_PA04(AIN4/REFB/SER0:0/TC0:0)_9") (pintype "bidirectional"))
    )
    (net (code "61") (name "unconnected-(U1-A4_PA05(AIN5{slash}SER0:1{slash}TC0:1)-Pad10)") (class "Default")
      (node (ref "U1") (pin "10") (pinfunction "A4_PA05(AIN5/SER0:1/TC0:1)_10") (pintype "bidirectional"))
    )
    (net (code "62") (name "unconnected-(U1-D8_PA06(AIN6{slash}SER0:2{slash}TC1:0)-Pad11)") (class "Default")
      (node (ref "U1") (pin "11") (pinfunction "D8_PA06(AIN6/SER0:2/TC1:0)_11") (pintype "bidirectional"))
    )
    (net (code "63") (name "unconnected-(U1-PA03(AIN1{slash}REFA)-Pad4)") (class "Default")
      (node (ref "U1") (pin "4") (pinfunction "PA03(AIN1/REFA)_4") (pintype "bidirectional"))
    )
    (net (code "64") (name "unconnected-(U1-PB10(SER4:2+)_MOSI-Pad19)") (class "Default")
      (node (ref "U1") (pin "19") (pinfunction "PB10(SER4:2+)_MOSI_19") (pintype "bidirectional"))
    )
    (net (code "65") (name "unconnected-(U2-CS-Pad7)") (class "Default")
      (node (ref "U2") (pin "7") (pinfunction "CS_7") (pintype "bidirectional"))
    )
    (net (code "66") (name "unconnected-(U2-NC-Pad3)") (class "Default")
      (node (ref "U2") (pin "3") (pinfunction "NC_3") (pintype "bidirectional"))
    )
    (net (code "67") (name "unconnected-(U2-NC-Pad10)") (class "Default")
      (node (ref "U2") (pin "10") (pinfunction "NC_10") (pintype "bidirectional"))
    )
    (net (code "68") (name "unconnected-(U2-NC-Pad11)") (class "Default")
      (node (ref "U2") (pin "11") (pinfunction "NC_11") (pintype "bidirectional"))
    )
    (net (code "69") (name "unconnected-(U2-VS-Pad6)") (class "Default")
      (node (ref "U2") (pin "6") (pinfunction "VS_6") (pintype "bidirectional"))
    )
  )
)
